# latoLV.net
KiCad netlist of a schematic drawn in EAGLE
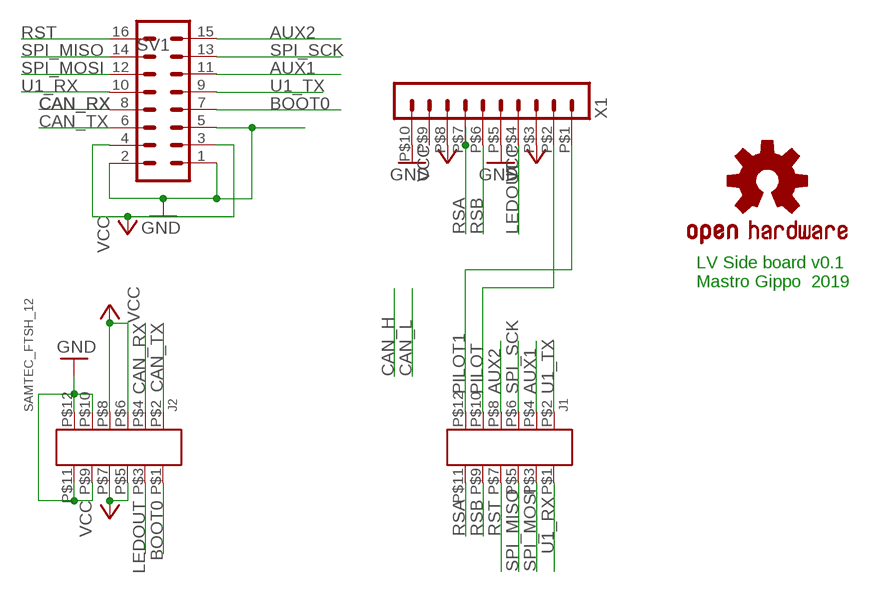
[diagram p0: schematic, sheet 1]

(export (version "E")
  (design (tool "Eeschema 10.0.6"))
  (components
    (comp (ref "J1")
      (value "SAMTEC_FTSH_12")
      (footprint "eagle-import:6X2_1MM")
      (libsource (lib "eagle-import") (part "SAMTEC_FTSH_12"))
    )
    (comp (ref "J2")
      (value "SAMTEC_FTSH_12")
      (footprint "eagle-import:6X2_1MM")
      (libsource (lib "eagle-import") (part "SAMTEC_FTSH_12"))
    )
    (comp (ref "SV1")
      (value "MA08-2")
      (footprint "eagle-import:MA08-2")
      (libsource (lib "eagle-import") (part "MA08-2"))
    )
    (comp (ref "U$1")
      (value "OSHW-LOGOS")
      (footprint "eagle-import:OSHW-LOGO-S")
      (libsource (lib "eagle-import") (part "OSHW-LOGOS"))
    )
    (comp (ref "X1")
      (value "HEADER_POS10_43045-1012")
      (footprint "eagle-import:43045-1012")
      (libsource (lib "eagle-import") (part "HEADER_POS10_?43045-1012"))
    )
  )
  (nets
    (net (code "1") (name "/AUX1") (class "Default")
      (node (ref "J1") (pin "P$4") (pinfunction "P$4_P$4") (pintype "bidirectional"))
      (node (ref "SV1") (pin "11") (pinfunction "11_11") (pintype "passive"))
    )
    (net (code "2") (name "/AUX2") (class "Default")
      (node (ref "J1") (pin "P$8") (pinfunction "P$8_P$8") (pintype "bidirectional"))
      (node (ref "SV1") (pin "15") (pinfunction "15_15") (pintype "passive"))
    )
    (net (code "3") (name "/BOOT0") (class "Default")
      (node (ref "J2") (pin "P$1") (pinfunction "P$1_P$1") (pintype "bidirectional"))
      (node (ref "SV1") (pin "7") (pinfunction "7_7") (pintype "passive"))
    )
    (net (code "6") (name "/CAN_RX") (class "Default")
      (node (ref "J2") (pin "P$4") (pinfunction "P$4_P$4") (pintype "bidirectional"))
      (node (ref "SV1") (pin "8") (pinfunction "8_8") (pintype "passive"))
    )
    (net (code "7") (name "/CAN_TX") (class "Default")
      (node (ref "J2") (pin "P$2") (pinfunction "P$2_P$2") (pintype "bidirectional"))
      (node (ref "SV1") (pin "6") (pinfunction "6_6") (pintype "passive"))
    )
    (net (code "8") (name "/LEDOUT") (class "Default")
      (node (ref "J2") (pin "P$3") (pinfunction "P$3_P$3") (pintype "bidirectional"))
      (node (ref "X1") (pin "P$4") (pinfunction "4_P$4") (pintype "passive"))
    )
    (net (code "9") (name "/PILOT") (class "Default")
      (node (ref "J1") (pin "P$10") (pinfunction "P$10_P$10") (pintype "bidirectional"))
      (node (ref "X1") (pin "P$2") (pinfunction "2_P$2") (pintype "passive"))
    )
    (net (code "10") (name "/PILOT1") (class "Default")
      (node (ref "J1") (pin "P$12") (pinfunction "P$12_P$12") (pintype "bidirectional"))
      (node (ref "X1") (pin "P$1") (pinfunction "1_P$1") (pintype "passive"))
    )
    (net (code "11") (name "/RSA") (class "Default")
      (node (ref "J1") (pin "P$11") (pinfunction "P$11_P$11") (pintype "bidirectional"))
      (node (ref "X1") (pin "P$7") (pinfunction "7_P$7") (pintype "passive"))
    )
    (net (code "12") (name "/RSB") (class "Default")
      (node (ref "J1") (pin "P$9") (pinfunction "P$9_P$9") (pintype "bidirectional"))
      (node (ref "X1") (pin "P$6") (pinfunction "6_P$6") (pintype "passive"))
    )
    (net (code "13") (name "/RST") (class "Default")
      (node (ref "J1") (pin "P$7") (pinfunction "P$7_P$7") (pintype "bidirectional"))
      (node (ref "SV1") (pin "16") (pinfunction "16_16") (pintype "passive"))
    )
    (net (code "14") (name "/SPI_MISO") (class "Default")
      (node (ref "J1") (pin "P$5") (pinfunction "P$5_P$5") (pintype "bidirectional"))
      (node (ref "SV1") (pin "14") (pinfunction "14_14") (pintype "passive"))
    )
    (net (code "15") (name "/SPI_MOSI") (class "Default")
      (node (ref "J1") (pin "P$3") (pinfunction "P$3_P$3") (pintype "bidirectional"))
      (node (ref "SV1") (pin "12") (pinfunction "12_12") (pintype "passive"))
    )
    (net (code "16") (name "/SPI_SCK") (class "Default")
      (node (ref "J1") (pin "P$6") (pinfunction "P$6_P$6") (pintype "bidirectional"))
      (node (ref "SV1") (pin "13") (pinfunction "13_13") (pintype "passive"))
    )
    (net (code "17") (name "/U1_RX") (class "Default")
      (node (ref "J1") (pin "P$1") (pinfunction "P$1_P$1") (pintype "bidirectional"))
      (node (ref "SV1") (pin "10") (pinfunction "10_10") (pintype "passive"))
    )
    (net (code "18") (name "/U1_TX") (class "Default")
      (node (ref "J1") (pin "P$2") (pinfunction "P$2_P$2") (pintype "bidirectional"))
      (node (ref "SV1") (pin "9") (pinfunction "9_9") (pintype "passive"))
    )
    (net (code "19") (name "GND") (class "Default")
      (node (ref "J2") (pin "P$10") (pinfunction "P$10_P$10") (pintype "bidirectional"))
      (node (ref "J2") (pin "P$11") (pinfunction "P$11_P$11") (pintype "bidirectional"))
      (node (ref "J2") (pin "P$12") (pinfunction "P$12_P$12") (pintype "bidirectional"))
      (node (ref "J2") (pin "P$9") (pinfunction "P$9_P$9") (pintype "bidirectional"))
      (node (ref "SV1") (pin "1") (pinfunction "1_1") (pintype "passive"))
      (node (ref "SV1") (pin "2") (pinfunction "2_2") (pintype "passive"))
      (node (ref "SV1") (pin "5") (pinfunction "5_5") (pintype "passive"))
      (node (ref "X1") (pin "P$10") (pinfunction "10_P$10") (pintype "passive"))
      (node (ref "X1") (pin "P$5") (pinfunction "5_P$5") (pintype "passive"))
    )
    (net (code "20") (name "VCC") (class "Default")
      (node (ref "J2") (pin "P$5") (pinfunction "P$5_P$5") (pintype "bidirectional"))
      (node (ref "J2") (pin "P$6") (pinfunction "P$6_P$6") (pintype "bidirectional"))
      (node (ref "J2") (pin "P$7") (pinfunction "P$7_P$7") (pintype "bidirectional"))
      (node (ref "J2") (pin "P$8") (pinfunction "P$8_P$8") (pintype "bidirectional"))
      (node (ref "SV1") (pin "3") (pinfunction "3_3") (pintype "passive"))
      (node (ref "SV1") (pin "4") (pinfunction "4_4") (pintype "passive"))
      (node (ref "X1") (pin "P$3") (pinfunction "3_P$3") (pintype "passive"))
      (node (ref "X1") (pin "P$8") (pinfunction "8_P$8") (pintype "passive"))
    )
    (net (code "21") (name "unconnected-(X1-9-PadP$9)") (class "Default")
      (node (ref "X1") (pin "P$9") (pinfunction "9_P$9") (pintype "passive"))
    )
  )
)
